# SSB_Transceiver_Supply_EMI_Filter.net
KiCad netlist of a schematic drawn in EAGLE
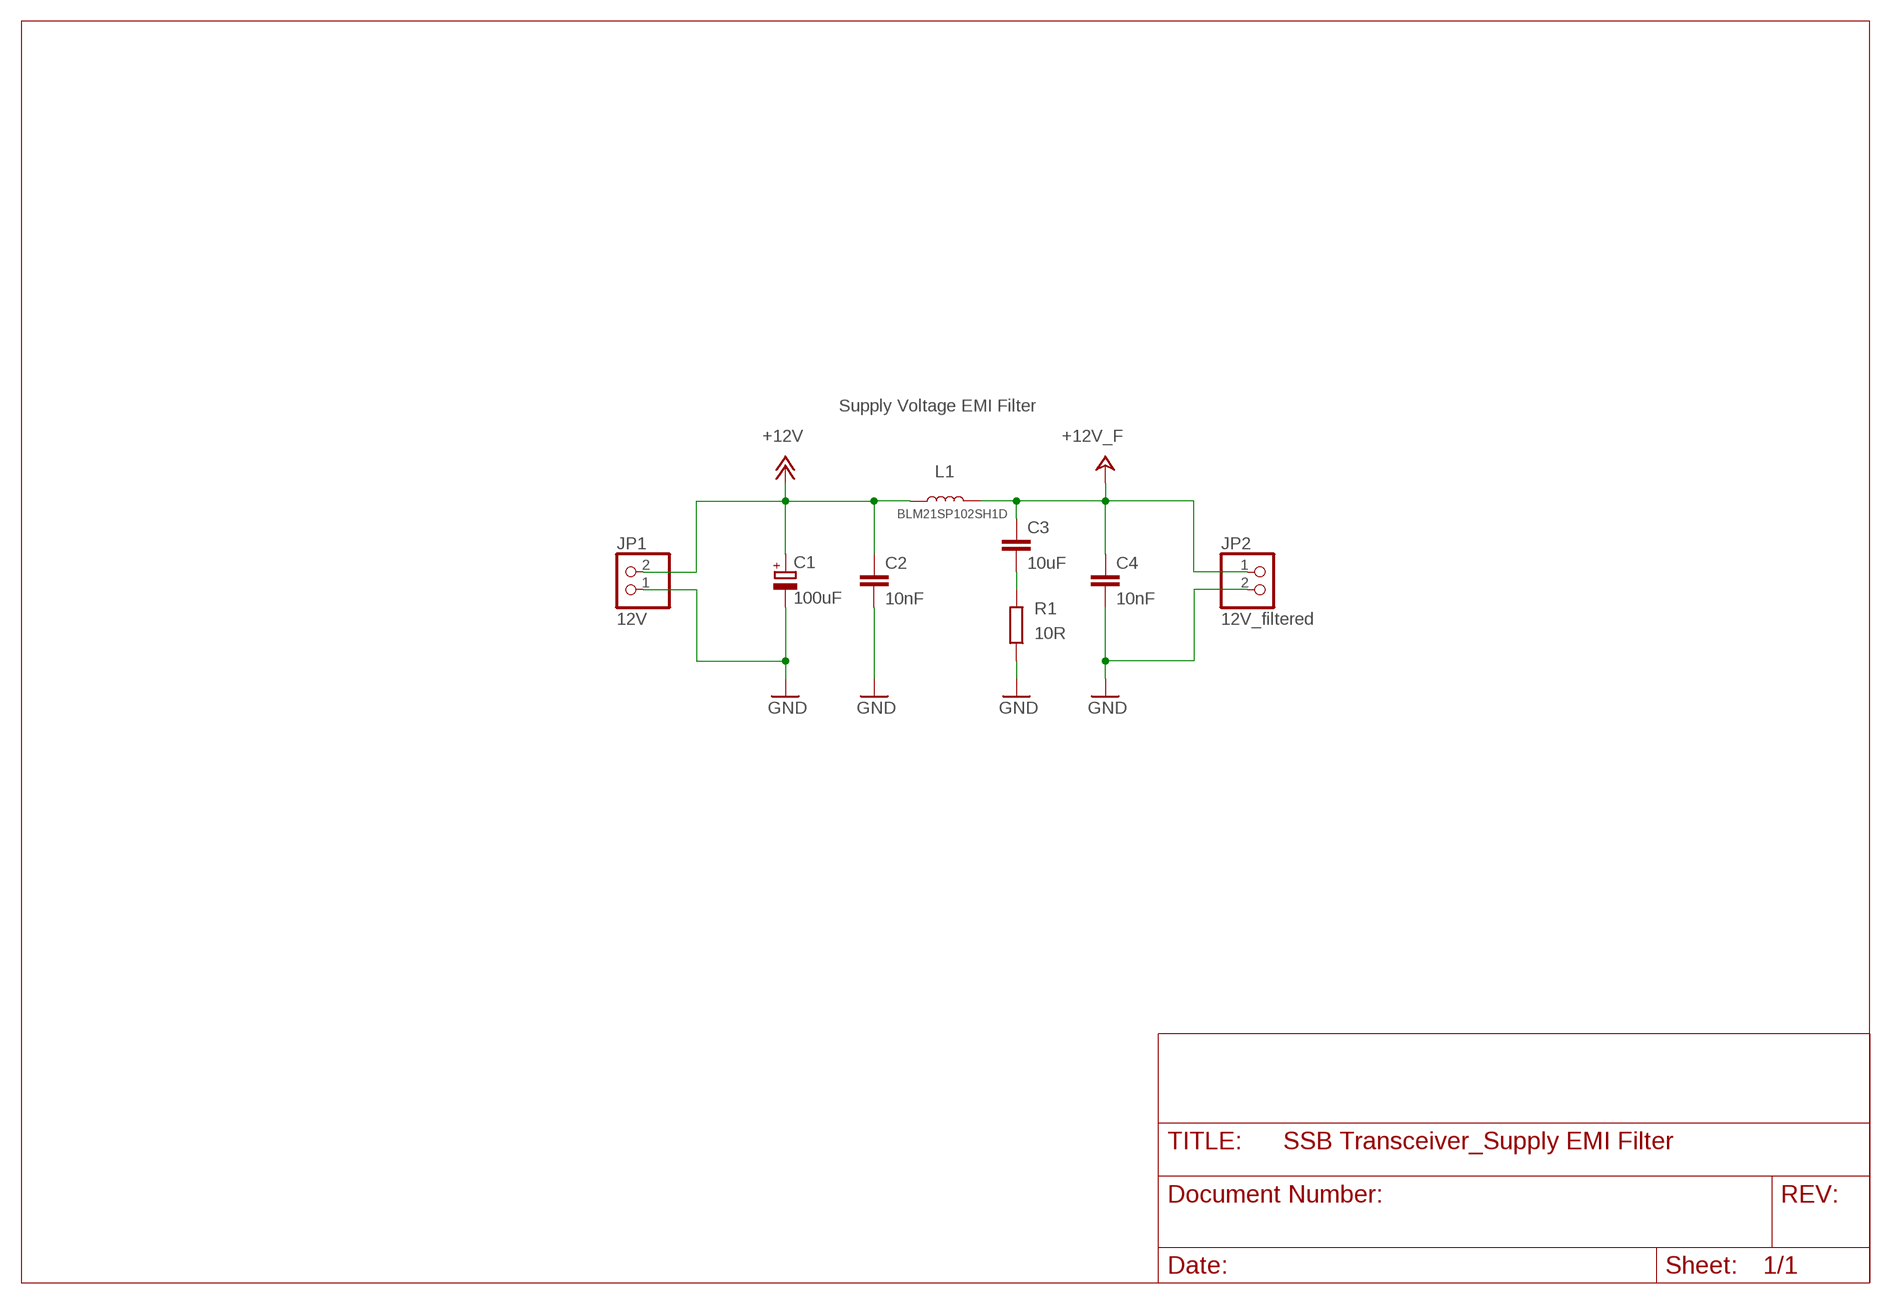
[diagram p0: schematic, sheet 1]

(export (version "E")
  (design (tool "Eeschema 10.0.6"))
  (components
    (comp (ref "C1")
      (value "100uF")
      (footprint "eagle-import:E2,5-7")
      (libsource (lib "eagle-import") (part "CPOL-EUE2.5-7"))
    )
    (comp (ref "C2")
      (value "10nF")
      (footprint "eagle-import:C0805")
      (libsource (lib "eagle-import") (part "C-EUC0805"))
    )
    (comp (ref "C3")
      (value "10uF")
      (footprint "eagle-import:C0805")
      (libsource (lib "eagle-import") (part "C-EUC0805"))
    )
    (comp (ref "C4")
      (value "10nF")
      (footprint "eagle-import:C0805")
      (libsource (lib "eagle-import") (part "C-EUC0805"))
    )
    (comp (ref "JP1")
      (value "12V")
      (footprint "eagle-import:1X02")
      (libsource (lib "eagle-import") (part "PINHD-1X2"))
    )
    (comp (ref "JP2")
      (value "12V_filtered")
      (footprint "eagle-import:1X02")
      (libsource (lib "eagle-import") (part "PINHD-1X2"))
    )
    (comp (ref "L1")
      (value "BLM21SP102SH1D")
      (footprint "eagle-import:0805")
      (libsource (lib "eagle-import") (part "INDUCTOR-0805-3.3UH"))
    )
    (comp (ref "R1")
      (value "10R")
      (footprint "eagle-import:R0805")
      (libsource (lib "eagle-import") (part "R-EU_R0805"))
    )
  )
  (nets
    (net (code "1") (name "+12V") (class "Default")
      (node (ref "C1") (pin "+") (pinfunction "+_+") (pintype "passive"))
      (node (ref "C2") (pin "1") (pinfunction "1_1") (pintype "passive"))
      (node (ref "JP1") (pin "2") (pinfunction "2_2") (pintype "passive"))
      (node (ref "L1") (pin "1") (pinfunction "1_1") (pintype "passive"))
    )
    (net (code "2") (name "+12V_F") (class "Default")
      (node (ref "C3") (pin "1") (pinfunction "1_1") (pintype "passive"))
      (node (ref "C4") (pin "1") (pinfunction "1_1") (pintype "passive"))
      (node (ref "JP2") (pin "1") (pinfunction "1_1") (pintype "passive"))
      (node (ref "L1") (pin "2") (pinfunction "2_2") (pintype "passive"))
    )
    (net (code "3") (name "GND") (class "Default")
      (node (ref "C1") (pin "-") (pinfunction "-_-") (pintype "passive"))
      (node (ref "C2") (pin "2") (pinfunction "2_2") (pintype "passive"))
      (node (ref "C4") (pin "2") (pinfunction "2_2") (pintype "passive"))
      (node (ref "JP1") (pin "1") (pinfunction "1_1") (pintype "passive"))
      (node (ref "JP2") (pin "2") (pinfunction "2_2") (pintype "passive"))
      (node (ref "R1") (pin "1") (pinfunction "1_1") (pintype "passive"))
    )
    (net (code "4") (name "Net-(C3-Pad2)") (class "Default")
      (node (ref "C3") (pin "2") (pinfunction "2_2") (pintype "passive"))
      (node (ref "R1") (pin "2") (pinfunction "2_2") (pintype "passive"))
    )
  )
)
